# Sheet2.net
KiCad netlist of a schematic drawn in Altium Designer
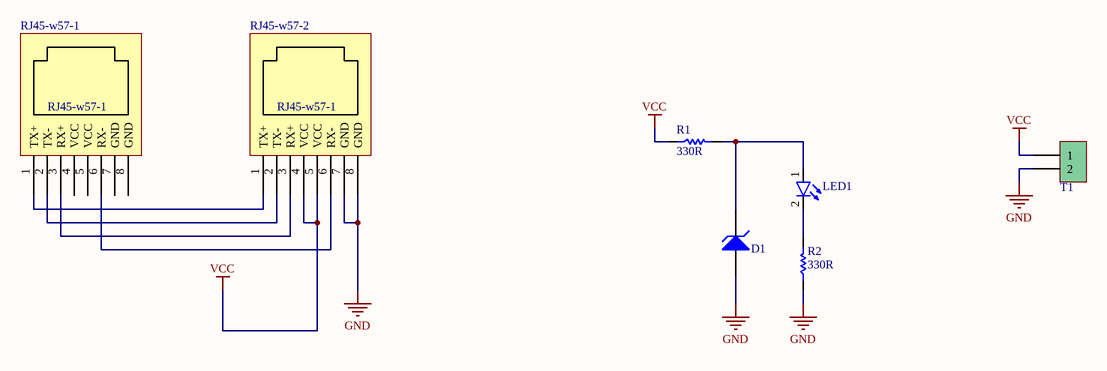
[diagram p0: Sheet2.SchDoc]

(export (version "E")
  (design (tool "Eeschema 10.0.6"))
  (components
    (comp (ref "D1")
      (value "Diode Zener")
      (footprint "Diode 1W")
      (description "Zener Diode")
      (fields (field (name "VOLTAGE") "12V") (field (name "DESIGNER") "Saeid Jorablo"))
      (libsource (lib "Electrovolt Lib") (part "Diode Zener"))
    )
    (comp (ref "LED1")
      (value "Red")
      (footprint "LED-5mm")
      (description "LED")
      (fields (field (name "DESIGNER") "Saeid Jorablo"))
      (libsource (lib "Electrovolt Lib") (part "LED"))
    )
    (comp (ref "R1")
      (value "330R")
      (footprint "RES 1206 (3216X08L)")
      (description "Resistor")
      (fields (field (name "TOLERANCE") "5%") (field (name "POWER") "1/8 W"))
      (libsource (lib "Electrovolt Lib") (part "Resistor"))
    )
    (comp (ref "R2")
      (value "330R")
      (footprint "RES 1206 (3216X08L)")
      (description "Resistor")
      (fields (field (name "TOLERANCE") "5%") (field (name "POWER") "1/8 W"))
      (libsource (lib "Electrovolt Lib") (part "Resistor"))
    )
    (comp (ref "RJ45-w57-1")
      (value "RJ45-w57-1")
      (footprint "rj45-w57-1")
      (libsource (lib "Schlib1") (part "RJ45-w57-1"))
    )
    (comp (ref "RJ45-w57-2")
      (value "RJ45-w57-1")
      (footprint "rj45-w57-1")
      (libsource (lib "Schlib1") (part "RJ45-w57-1"))
    )
    (comp (ref "T1")
      (value "Phoenix terminal")
      (footprint "phoenix terminal 2")
      (description "Terminal 2 Pin")
      (fields (field (name "DESIGNER") "Seyed Mohsen Ghasemain") (field (name "E-MAIL") "picpars@gmail.com"))
      (libsource (lib "usefully_Library") (part "Phoenix terminal 2"))
    )
  )
  (nets
    (net (code "1") (name "GND") (class "Default")
      (node (ref "D1") (pin "1") (pinfunction "A_1") (pintype "passive"))
      (node (ref "R2") (pin "1") (pinfunction "1_1") (pintype "passive"))
      (node (ref "RJ45-w57-2") (pin "7") (pinfunction "GND_7") (pintype "passive"))
      (node (ref "RJ45-w57-2") (pin "8") (pinfunction "GND_8") (pintype "passive"))
      (node (ref "T1") (pin "2") (pinfunction "2_2") (pintype "passive"))
    )
    (net (code "2") (name "Net-(D1-K)") (class "Default")
      (node (ref "D1") (pin "2") (pinfunction "K_2") (pintype "passive"))
      (node (ref "LED1") (pin "1") (pinfunction "A_1") (pintype "passive"))
      (node (ref "R1") (pin "2") (pinfunction "2_2") (pintype "passive"))
    )
    (net (code "3") (name "Net-(LED1-K)") (class "Default")
      (node (ref "LED1") (pin "2") (pinfunction "K_2") (pintype "passive"))
      (node (ref "R2") (pin "2") (pinfunction "2_2") (pintype "passive"))
    )
    (net (code "4") (name "Net-(RJ45-w57-1-RX+)") (class "Default")
      (node (ref "RJ45-w57-1") (pin "3") (pinfunction "RX+_3") (pintype "passive"))
      (node (ref "RJ45-w57-2") (pin "3") (pinfunction "RX+_3") (pintype "passive"))
    )
    (net (code "5") (name "Net-(RJ45-w57-1-RX-)") (class "Default")
      (node (ref "RJ45-w57-1") (pin "6") (pinfunction "RX-_6") (pintype "passive"))
      (node (ref "RJ45-w57-2") (pin "6") (pinfunction "RX-_6") (pintype "passive"))
    )
    (net (code "6") (name "Net-(RJ45-w57-1-TX+)") (class "Default")
      (node (ref "RJ45-w57-1") (pin "1") (pinfunction "TX+_1") (pintype "passive"))
      (node (ref "RJ45-w57-2") (pin "1") (pinfunction "TX+_1") (pintype "passive"))
    )
    (net (code "7") (name "Net-(RJ45-w57-1-TX-)") (class "Default")
      (node (ref "RJ45-w57-1") (pin "2") (pinfunction "TX-_2") (pintype "passive"))
      (node (ref "RJ45-w57-2") (pin "2") (pinfunction "TX-_2") (pintype "passive"))
    )
    (net (code "8") (name "VCC") (class "Default")
      (node (ref "R1") (pin "1") (pinfunction "1_1") (pintype "passive"))
      (node (ref "RJ45-w57-2") (pin "4") (pinfunction "VCC_4") (pintype "passive"))
      (node (ref "RJ45-w57-2") (pin "5") (pinfunction "VCC_5") (pintype "passive"))
      (node (ref "T1") (pin "1") (pinfunction "1_1") (pintype "passive"))
    )
    (net (code "9") (name "unconnected-(RJ45-w57-1-GND-Pad7)") (class "Default")
      (node (ref "RJ45-w57-1") (pin "7") (pinfunction "GND_7") (pintype "passive"))
    )
    (net (code "10") (name "unconnected-(RJ45-w57-1-GND-Pad8)") (class "Default")
      (node (ref "RJ45-w57-1") (pin "8") (pinfunction "GND_8") (pintype "passive"))
    )
    (net (code "11") (name "unconnected-(RJ45-w57-1-VCC-Pad4)") (class "Default")
      (node (ref "RJ45-w57-1") (pin "4") (pinfunction "VCC_4") (pintype "passive"))
    )
    (net (code "12") (name "unconnected-(RJ45-w57-1-VCC-Pad5)") (class "Default")
      (node (ref "RJ45-w57-1") (pin "5") (pinfunction "VCC_5") (pintype "passive"))
    )
  )
)
